# Drivetrain_control.net
KiCad netlist of a schematic drawn in EAGLE
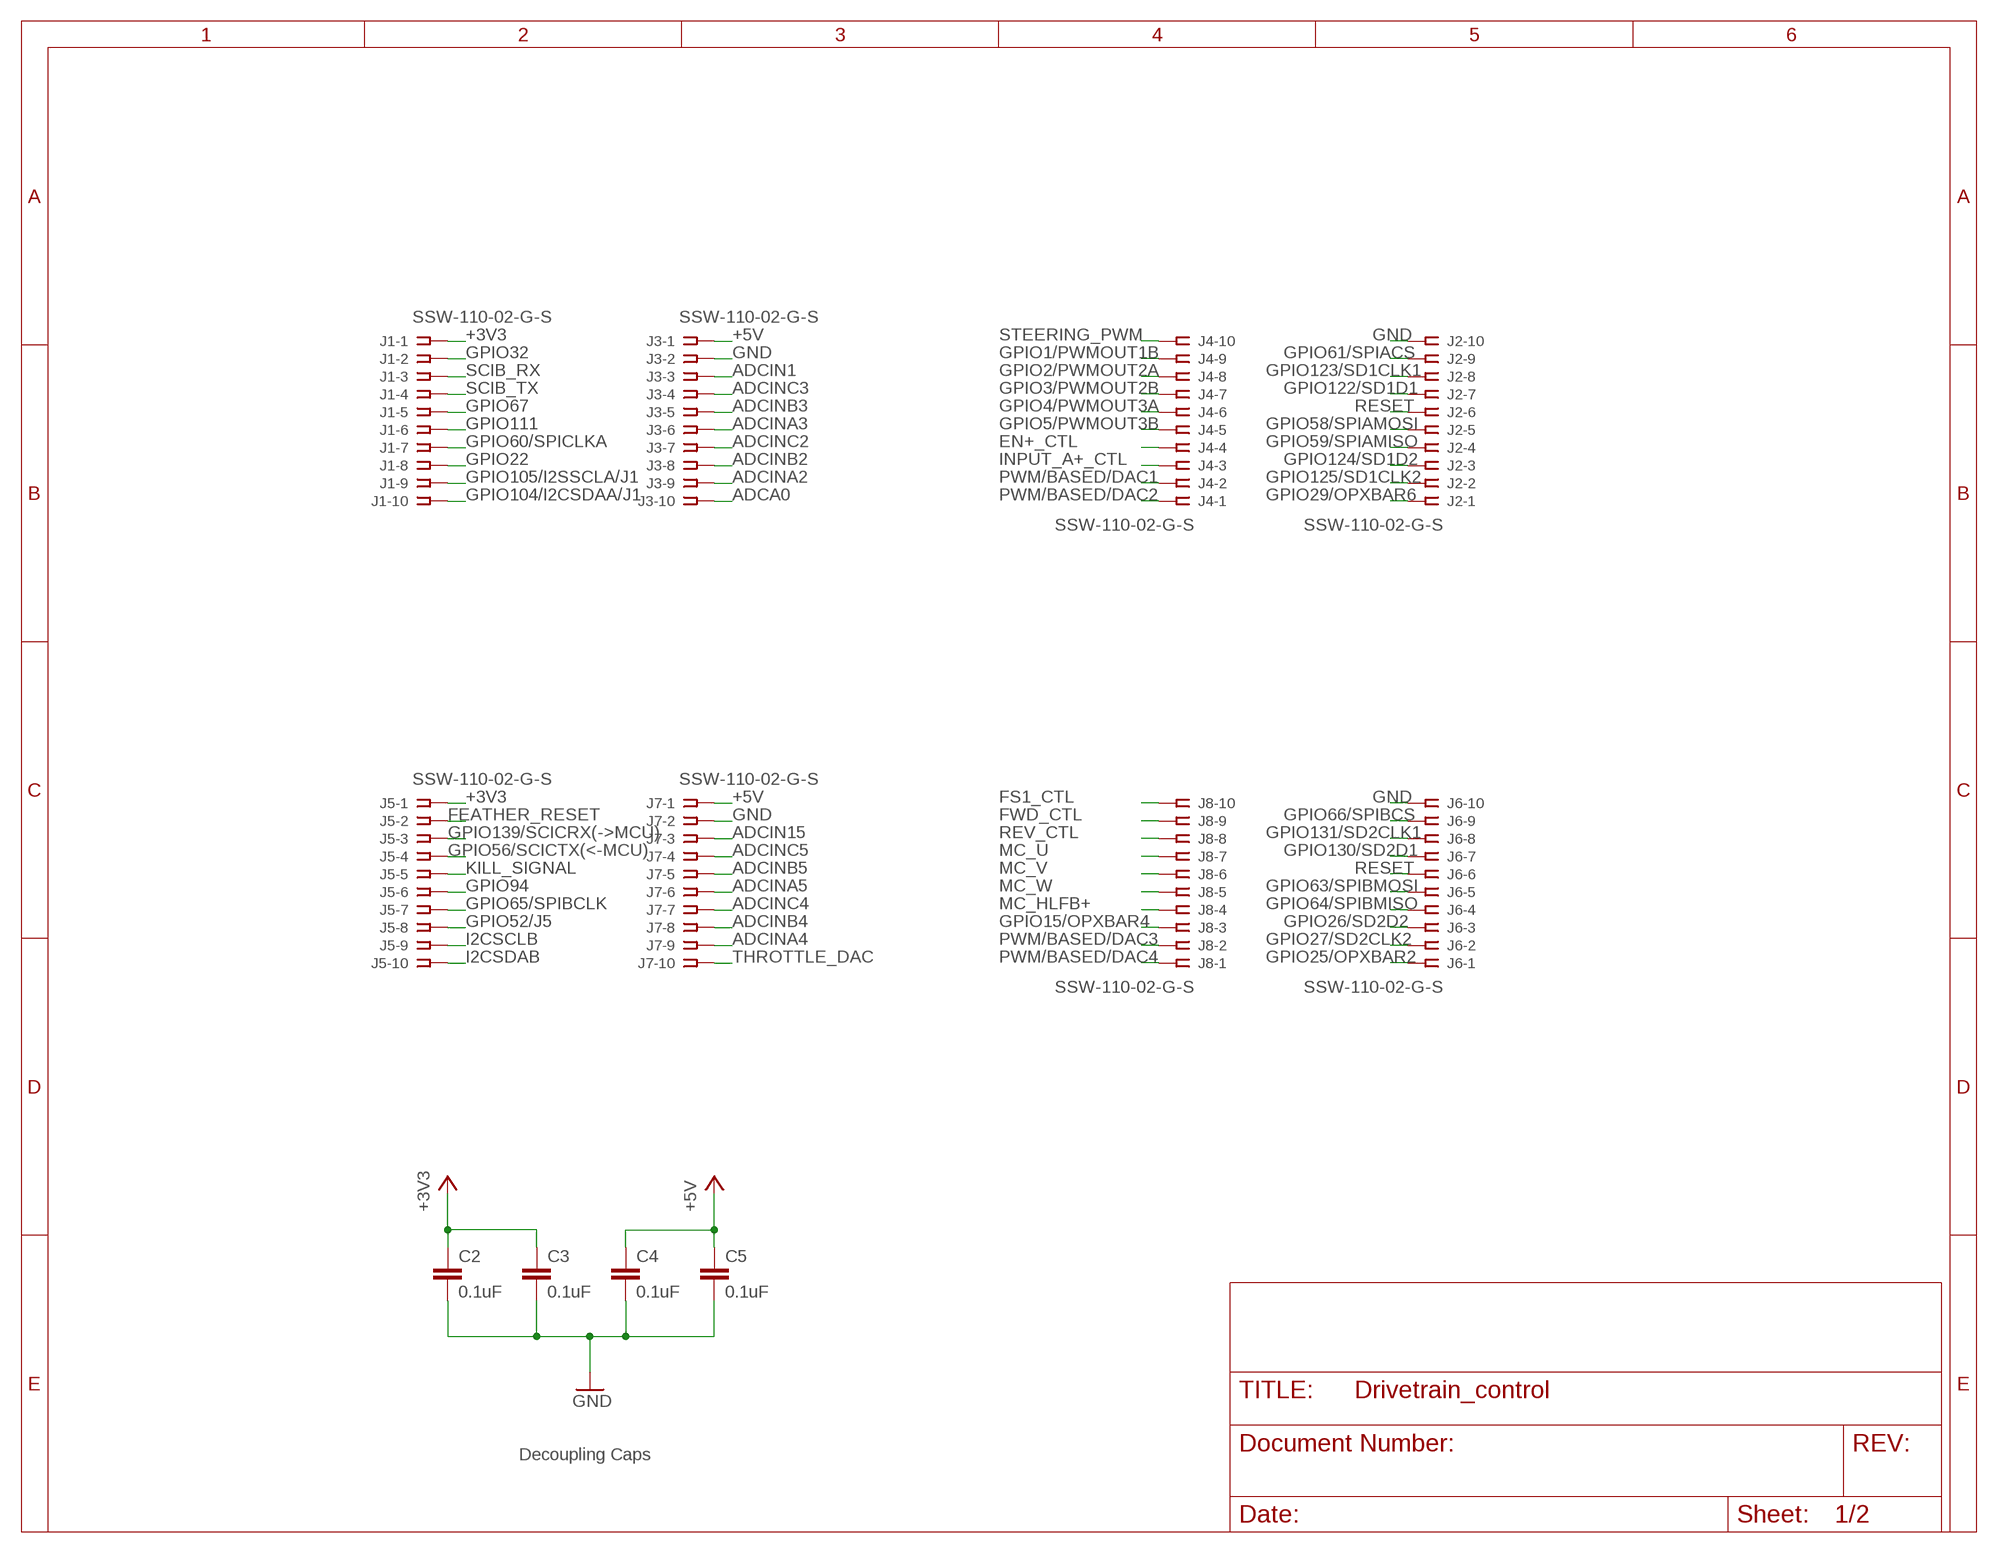
[diagram p0: schematic, sheet 1]
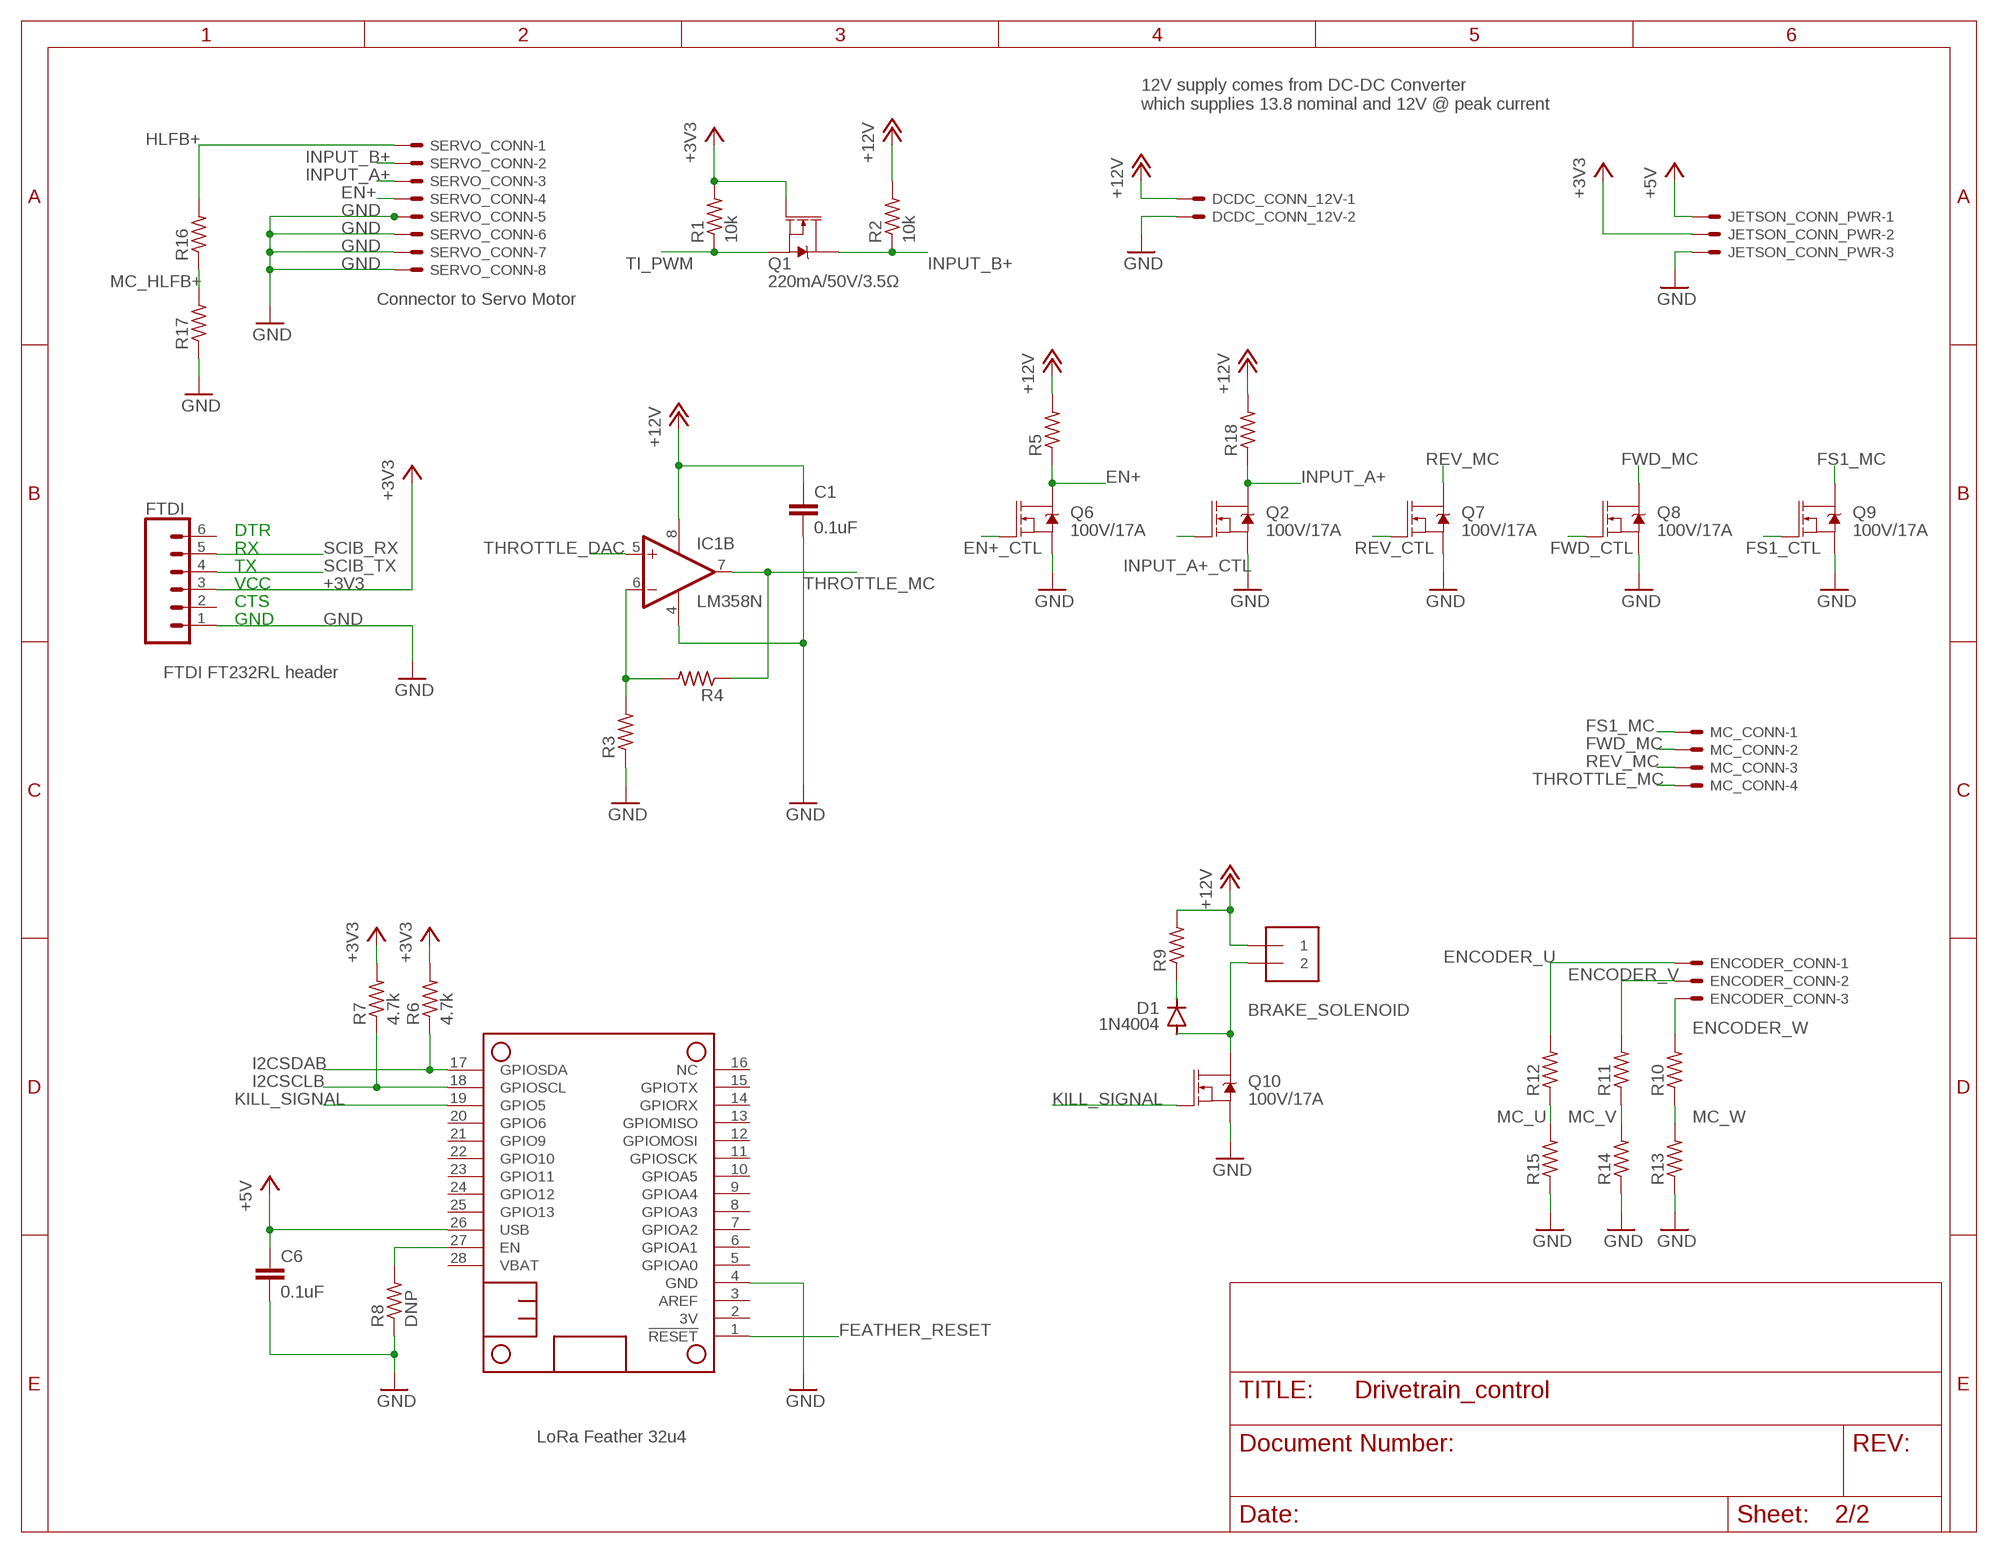
[diagram p1: schematic, sheet 2]

(export (version "E")
  (design (tool "Eeschema 10.0.6"))
  (components
    (comp (ref "BRAKE_CONN")
      (value "1X2-3.5MM")
      (footprint "eagle-import:1X2-3.5MM")
      (libsource (lib "eagle-import") (part "1X2-3.5MM"))
    )
    (comp (ref "C1")
      (value "0.1uF")
      (footprint "eagle-import:C0805")
      (libsource (lib "eagle-import") (part "C"))
    )
    (comp (ref "C6")
      (value "0.1uF")
      (footprint "eagle-import:C0805")
      (libsource (lib "eagle-import") (part "C"))
    )
    (comp (ref "D1")
      (value "1N4004")
      (footprint "eagle-import:DO41-10")
      (libsource (lib "eagle-import") (part "1N4004"))
    )
    (comp (ref "DCDC_CONN_12V")
      (value "22-23-2021")
      (footprint "eagle-import:22-23-2021")
      (fields (field (name "MF") "MOLEX"))
      (libsource (lib "eagle-import") (part "22-23-2021"))
    )
    (comp (ref "ENCODER_CONN")
      (value "22-23-2031")
      (footprint "eagle-import:22-23-2031")
      (fields (field (name "MF") "MOLEX"))
      (libsource (lib "eagle-import") (part "22-23-2031"))
    )
    (comp (ref "FTDI")
      (value "CONN_06LONGPADS")
      (footprint "eagle-import:1X06_LONGPADS")
      (libsource (lib "eagle-import") (part "CONN_06LONGPADS"))
    )
    (comp (ref "IC1")
      (value "LM358N")
      (footprint "eagle-import:DIL08")
      (libsource (lib "eagle-import") (part "LM358N"))
    )
    (comp (ref "JETSON_CONN_PWR")
      (value "22-23-2031")
      (footprint "eagle-import:22-23-2031")
      (fields (field (name "MF") "MOLEX"))
      (libsource (lib "eagle-import") (part "22-23-2031"))
    )
    (comp (ref "MC_CONN")
      (value "22-23-2041")
      (footprint "eagle-import:22-23-2041")
      (fields (field (name "MF") "MOLEX"))
      (libsource (lib "eagle-import") (part "22-23-2041"))
    )
    (comp (ref "MS1")
      (value "FEATHERWING_NODIM")
      (footprint "eagle-import:FEATHERWING_DIM")
      (libsource (lib "eagle-import") (part "FEATHERWING_NODIM"))
    )
    (comp (ref "Q1")
      (value "220mA/50V/3.5Ω")
      (footprint "eagle-import:SOT23-3")
      (libsource (lib "eagle-import") (part "MOSFET-NCH-BSS138"))
    )
    (comp (ref "Q2")
      (value "100V/17A")
      (footprint "eagle-import:TO220V")
      (libsource (lib "eagle-import") (part "MOSFET-NCH-FQP30N06L"))
    )
    (comp (ref "Q6")
      (value "100V/17A")
      (footprint "eagle-import:TO220V")
      (libsource (lib "eagle-import") (part "MOSFET-NCH-FQP30N06L"))
    )
    (comp (ref "Q7")
      (value "100V/17A")
      (footprint "eagle-import:TO220V")
      (libsource (lib "eagle-import") (part "MOSFET-NCH-FQP30N06L"))
    )
    (comp (ref "Q8")
      (value "100V/17A")
      (footprint "eagle-import:TO220V")
      (libsource (lib "eagle-import") (part "MOSFET-NCH-FQP30N06L"))
    )
    (comp (ref "Q9")
      (value "100V/17A")
      (footprint "eagle-import:TO220V")
      (libsource (lib "eagle-import") (part "MOSFET-NCH-FQP30N06L"))
    )
    (comp (ref "Q10")
      (value "100V/17A")
      (footprint "eagle-import:TO220V")
      (libsource (lib "eagle-import") (part "MOSFET-NCH-FQP30N06L"))
    )
    (comp (ref "R1")
      (value "10k")
      (footprint "eagle-import:R0805")
      (libsource (lib "eagle-import") (part "R-US_R0805"))
    )
    (comp (ref "R2")
      (value "10k")
      (footprint "eagle-import:R0805")
      (libsource (lib "eagle-import") (part "R-US_R0805"))
    )
    (comp (ref "R3")
      (value "R-US_R0805")
      (footprint "eagle-import:R0805")
      (libsource (lib "eagle-import") (part "R-US_R0805"))
    )
    (comp (ref "R4")
      (value "R-US_R0805")
      (footprint "eagle-import:R0805")
      (libsource (lib "eagle-import") (part "R-US_R0805"))
    )
    (comp (ref "R5")
      (value "R-US_R0805")
      (footprint "eagle-import:R0805")
      (libsource (lib "eagle-import") (part "R-US_R0805"))
    )
    (comp (ref "R6")
      (value "4.7k")
      (footprint "eagle-import:R0805")
      (libsource (lib "eagle-import") (part "R-US_R0805"))
    )
    (comp (ref "R7")
      (value "4.7k")
      (footprint "eagle-import:R0805")
      (libsource (lib "eagle-import") (part "R-US_R0805"))
    )
    (comp (ref "R8")
      (value "DNP")
      (footprint "eagle-import:R0805")
      (libsource (lib "eagle-import") (part "R-US_R0805"))
    )
    (comp (ref "R9")
      (value "R-US_R0805")
      (footprint "eagle-import:R0805")
      (libsource (lib "eagle-import") (part "R-US_R0805"))
    )
    (comp (ref "R10")
      (value "R-US_R0805")
      (footprint "eagle-import:R0805")
      (libsource (lib "eagle-import") (part "R-US_R0805"))
    )
    (comp (ref "R11")
      (value "R-US_R0805")
      (footprint "eagle-import:R0805")
      (libsource (lib "eagle-import") (part "R-US_R0805"))
    )
    (comp (ref "R12")
      (value "R-US_R0805")
      (footprint "eagle-import:R0805")
      (libsource (lib "eagle-import") (part "R-US_R0805"))
    )
    (comp (ref "R13")
      (value "R-US_R0805")
      (footprint "eagle-import:R0805")
      (libsource (lib "eagle-import") (part "R-US_R0805"))
    )
    (comp (ref "R14")
      (value "R-US_R0805")
      (footprint "eagle-import:R0805")
      (libsource (lib "eagle-import") (part "R-US_R0805"))
    )
    (comp (ref "R15")
      (value "R-US_R0805")
      (footprint "eagle-import:R0805")
      (libsource (lib "eagle-import") (part "R-US_R0805"))
    )
    (comp (ref "R16")
      (value "R-US_R0805")
      (footprint "eagle-import:R0805")
      (libsource (lib "eagle-import") (part "R-US_R0805"))
    )
    (comp (ref "R17")
      (value "R-US_R0805")
      (footprint "eagle-import:R0805")
      (libsource (lib "eagle-import") (part "R-US_R0805"))
    )
    (comp (ref "R18")
      (value "R-US_R0805")
      (footprint "eagle-import:R0805")
      (libsource (lib "eagle-import") (part "R-US_R0805"))
    )
    (comp (ref "SERVO_CONN")
      (value "5566-8")
      (footprint "eagle-import:5566-8")
      (fields (field (name "MF") "MOLEX"))
      (libsource (lib "eagle-import") (part "5566-8"))
    )
    (comp (ref "C2")
      (value "0.1uF")
      (footprint "eagle-import:C0805")
      (libsource (lib "eagle-import") (part "C"))
    )
    (comp (ref "C3")
      (value "0.1uF")
      (footprint "eagle-import:C0805")
      (libsource (lib "eagle-import") (part "C"))
    )
    (comp (ref "C4")
      (value "0.1uF")
      (footprint "eagle-import:C0805")
      (libsource (lib "eagle-import") (part "C"))
    )
    (comp (ref "C5")
      (value "0.1uF")
      (footprint "eagle-import:C0805")
      (libsource (lib "eagle-import") (part "C"))
    )
    (comp (ref "J1")
      (value "SSW-110-02-G-S")
      (footprint "eagle-import:SSW-110-02-G-S")
      (fields (field (name "MF") "Samtec Inc."))
      (libsource (lib "eagle-import") (part "SSW-110-02-G-S"))
    )
    (comp (ref "J2")
      (value "SSW-110-02-G-S")
      (footprint "eagle-import:SSW-110-02-G-S")
      (fields (field (name "MF") "Samtec Inc."))
      (libsource (lib "eagle-import") (part "SSW-110-02-G-S"))
    )
    (comp (ref "J3")
      (value "SSW-110-02-G-S")
      (footprint "eagle-import:SSW-110-02-G-S")
      (fields (field (name "MF") "Samtec Inc."))
      (libsource (lib "eagle-import") (part "SSW-110-02-G-S"))
    )
    (comp (ref "J4")
      (value "SSW-110-02-G-S")
      (footprint "eagle-import:SSW-110-02-G-S")
      (fields (field (name "MF") "Samtec Inc."))
      (libsource (lib "eagle-import") (part "SSW-110-02-G-S"))
    )
    (comp (ref "J5")
      (value "SSW-110-02-G-S")
      (footprint "eagle-import:SSW-110-02-G-S")
      (fields (field (name "MF") "Samtec Inc."))
      (libsource (lib "eagle-import") (part "SSW-110-02-G-S"))
    )
    (comp (ref "J6")
      (value "SSW-110-02-G-S")
      (footprint "eagle-import:SSW-110-02-G-S")
      (fields (field (name "MF") "Samtec Inc."))
      (libsource (lib "eagle-import") (part "SSW-110-02-G-S"))
    )
    (comp (ref "J7")
      (value "SSW-110-02-G-S")
      (footprint "eagle-import:SSW-110-02-G-S")
      (fields (field (name "MF") "Samtec Inc."))
      (libsource (lib "eagle-import") (part "SSW-110-02-G-S"))
    )
    (comp (ref "J8")
      (value "SSW-110-02-G-S")
      (footprint "eagle-import:SSW-110-02-G-S")
      (fields (field (name "MF") "Samtec Inc."))
      (libsource (lib "eagle-import") (part "SSW-110-02-G-S"))
    )
  )
  (nets
    (net (code "1") (name "+3V3") (class "Default")
      (node (ref "C2") (pin "1") (pinfunction "1_1") (pintype "passive"))
      (node (ref "C3") (pin "1") (pinfunction "1_1") (pintype "passive"))
      (node (ref "FTDI") (pin "3") (pinfunction "3_3") (pintype "passive"))
      (node (ref "J1") (pin "1") (pinfunction "1_1") (pintype "passive"))
      (node (ref "J5") (pin "1") (pinfunction "1_1") (pintype "passive"))
      (node (ref "JETSON_CONN_PWR") (pin "2") (pinfunction "S_2") (pintype "passive"))
      (node (ref "Q1") (pin "1") (pinfunction "G_1") (pintype "bidirectional"))
      (node (ref "R1") (pin "2") (pinfunction "2_2") (pintype "passive"))
      (node (ref "R6") (pin "2") (pinfunction "2_2") (pintype "passive"))
      (node (ref "R7") (pin "2") (pinfunction "2_2") (pintype "passive"))
    )
    (net (code "2") (name "+5V") (class "Default")
      (node (ref "C4") (pin "1") (pinfunction "1_1") (pintype "passive"))
      (node (ref "C5") (pin "1") (pinfunction "1_1") (pintype "passive"))
      (node (ref "C6") (pin "1") (pinfunction "1_1") (pintype "passive"))
      (node (ref "J3") (pin "1") (pinfunction "1_1") (pintype "passive"))
      (node (ref "J7") (pin "1") (pinfunction "1_1") (pintype "passive"))
      (node (ref "JETSON_CONN_PWR") (pin "1") (pinfunction "S_1") (pintype "passive"))
      (node (ref "MS1") (pin "26") (pinfunction "USB_26") (pintype "power_in"))
    )
    (net (code "3") (name "+12V") (class "Default")
      (node (ref "BRAKE_CONN") (pin "1") (pinfunction "1_1") (pintype "passive"))
      (node (ref "C1") (pin "1") (pinfunction "1_1") (pintype "passive"))
      (node (ref "DCDC_CONN_12V") (pin "1") (pinfunction "S_1") (pintype "passive"))
      (node (ref "IC1") (pin "8") (pinfunction "V+_8") (pintype "power_in"))
      (node (ref "R18") (pin "2") (pinfunction "2_2") (pintype "passive"))
      (node (ref "R2") (pin "2") (pinfunction "2_2") (pintype "passive"))
      (node (ref "R5") (pin "2") (pinfunction "2_2") (pintype "passive"))
      (node (ref "R9") (pin "2") (pinfunction "2_2") (pintype "passive"))
    )
    (net (code "4") (name "3V") (class "Default")
      (node (ref "MS1") (pin "2") (pinfunction "3V_2") (pintype "power_in"))
    )
    (net (code "5") (name "ADCA0") (class "Default")
      (node (ref "J3") (pin "10") (pinfunction "1_10") (pintype "passive"))
    )
    (net (code "6") (name "ADCIN1") (class "Default")
      (node (ref "J3") (pin "3") (pinfunction "1_3") (pintype "passive"))
    )
    (net (code "7") (name "ADCIN15") (class "Default")
      (node (ref "J7") (pin "3") (pinfunction "1_3") (pintype "passive"))
    )
    (net (code "8") (name "ADCINA2") (class "Default")
      (node (ref "J3") (pin "9") (pinfunction "1_9") (pintype "passive"))
    )
    (net (code "9") (name "ADCINA3") (class "Default")
      (node (ref "J3") (pin "6") (pinfunction "1_6") (pintype "passive"))
    )
    (net (code "10") (name "ADCINA4") (class "Default")
      (node (ref "J7") (pin "9") (pinfunction "1_9") (pintype "passive"))
    )
    (net (code "11") (name "ADCINA5") (class "Default")
      (node (ref "J7") (pin "6") (pinfunction "1_6") (pintype "passive"))
    )
    (net (code "12") (name "ADCINB2") (class "Default")
      (node (ref "J3") (pin "8") (pinfunction "1_8") (pintype "passive"))
    )
    (net (code "13") (name "ADCINB3") (class "Default")
      (node (ref "J3") (pin "5") (pinfunction "1_5") (pintype "passive"))
    )
    (net (code "14") (name "ADCINB4") (class "Default")
      (node (ref "J7") (pin "8") (pinfunction "1_8") (pintype "passive"))
    )
    (net (code "15") (name "ADCINB5") (class "Default")
      (node (ref "J7") (pin "5") (pinfunction "1_5") (pintype "passive"))
    )
    (net (code "16") (name "ADCINC2") (class "Default")
      (node (ref "J3") (pin "7") (pinfunction "1_7") (pintype "passive"))
    )
    (net (code "17") (name "ADCINC3") (class "Default")
      (node (ref "J3") (pin "4") (pinfunction "1_4") (pintype "passive"))
    )
    (net (code "18") (name "ADCINC4") (class "Default")
      (node (ref "J7") (pin "7") (pinfunction "1_7") (pintype "passive"))
    )
    (net (code "19") (name "ADCINC5") (class "Default")
      (node (ref "J7") (pin "4") (pinfunction "1_4") (pintype "passive"))
    )
    (net (code "20") (name "BRAKE_SOLENOID") (class "Default")
      (node (ref "BRAKE_CONN") (pin "2") (pinfunction "2_2") (pintype "passive"))
      (node (ref "D1") (pin "A") (pinfunction "A_A") (pintype "passive"))
      (node (ref "Q10") (pin "2") (pinfunction "D_2") (pintype "bidirectional"))
    )
    (net (code "21") (name "EN+") (class "Default")
      (node (ref "Q6") (pin "2") (pinfunction "D_2") (pintype "bidirectional"))
      (node (ref "R5") (pin "1") (pinfunction "1_1") (pintype "passive"))
      (node (ref "SERVO_CONN") (pin "4") (pinfunction "S_4") (pintype "passive"))
    )
    (net (code "22") (name "EN+_CTL") (class "Default")
      (node (ref "J4") (pin "4") (pinfunction "1_4") (pintype "passive"))
      (node (ref "Q6") (pin "1") (pinfunction "G_1") (pintype "bidirectional"))
    )
    (net (code "23") (name "ENCODER_U") (class "Default")
      (node (ref "ENCODER_CONN") (pin "1") (pinfunction "S_1") (pintype "passive"))
      (node (ref "R12") (pin "2") (pinfunction "2_2") (pintype "passive"))
    )
    (net (code "24") (name "ENCODER_V") (class "Default")
      (node (ref "ENCODER_CONN") (pin "2") (pinfunction "S_2") (pintype "passive"))
      (node (ref "R11") (pin "2") (pinfunction "2_2") (pintype "passive"))
    )
    (net (code "25") (name "ENCODER_W") (class "Default")
      (node (ref "ENCODER_CONN") (pin "3") (pinfunction "S_3") (pintype "passive"))
      (node (ref "R10") (pin "2") (pinfunction "2_2") (pintype "passive"))
    )
    (net (code "26") (name "FEATHER_RESET") (class "Default")
      (node (ref "J5") (pin "2") (pinfunction "1_2") (pintype "passive"))
      (node (ref "MS1") (pin "1") (pinfunction "~{RESET}_1") (pintype "input"))
    )
    (net (code "27") (name "FS1_CTL") (class "Default")
      (node (ref "J8") (pin "10") (pinfunction "1_10") (pintype "passive"))
      (node (ref "Q9") (pin "1") (pinfunction "G_1") (pintype "bidirectional"))
    )
    (net (code "28") (name "FS1_MC") (class "Default")
      (node (ref "MC_CONN") (pin "1") (pinfunction "S_1") (pintype "passive"))
      (node (ref "Q9") (pin "2") (pinfunction "D_2") (pintype "bidirectional"))
    )
    (net (code "29") (name "FWD_CTL") (class "Default")
      (node (ref "J8") (pin "9") (pinfunction "1_9") (pintype "passive"))
      (node (ref "Q8") (pin "1") (pinfunction "G_1") (pintype "bidirectional"))
    )
    (net (code "30") (name "FWD_MC") (class "Default")
      (node (ref "MC_CONN") (pin "2") (pinfunction "S_2") (pintype "passive"))
      (node (ref "Q8") (pin "2") (pinfunction "D_2") (pintype "bidirectional"))
    )
    (net (code "31") (name "GND") (class "Default")
      (node (ref "C1") (pin "2") (pinfunction "2_2") (pintype "passive"))
      (node (ref "C2") (pin "2") (pinfunction "2_2") (pintype "passive"))
      (node (ref "C3") (pin "2") (pinfunction "2_2") (pintype "passive"))
      (node (ref "C4") (pin "2") (pinfunction "2_2") (pintype "passive"))
      (node (ref "C5") (pin "2") (pinfunction "2_2") (pintype "passive"))
      (node (ref "C6") (pin "2") (pinfunction "2_2") (pintype "passive"))
      (node (ref "DCDC_CONN_12V") (pin "2") (pinfunction "S_2") (pintype "passive"))
      (node (ref "FTDI") (pin "1") (pinfunction "1_1") (pintype "passive"))
      (node (ref "IC1") (pin "4") (pinfunction "V-_4") (pintype "power_in"))
      (node (ref "J2") (pin "10") (pinfunction "1_10") (pintype "passive"))
      (node (ref "J3") (pin "2") (pinfunction "1_2") (pintype "passive"))
      (node (ref "J6") (pin "10") (pinfunction "1_10") (pintype "passive"))
      (node (ref "J7") (pin "2") (pinfunction "1_2") (pintype "passive"))
      (node (ref "JETSON_CONN_PWR") (pin "3") (pinfunction "S_3") (pintype "passive"))
      (node (ref "MS1") (pin "4") (pinfunction "GND_4") (pintype "power_in"))
      (node (ref "Q10") (pin "3") (pinfunction "S_3") (pintype "bidirectional"))
      (node (ref "Q2") (pin "3") (pinfunction "S_3") (pintype "bidirectional"))
      (node (ref "Q6") (pin "3") (pinfunction "S_3") (pintype "bidirectional"))
      (node (ref "Q7") (pin "3") (pinfunction "S_3") (pintype "bidirectional"))
      (node (ref "Q8") (pin "3") (pinfunction "S_3") (pintype "bidirectional"))
      (node (ref "Q9") (pin "3") (pinfunction "S_3") (pintype "bidirectional"))
      (node (ref "R13") (pin "1") (pinfunction "1_1") (pintype "passive"))
      (node (ref "R14") (pin "1") (pinfunction "1_1") (pintype "passive"))
      (node (ref "R15") (pin "1") (pinfunction "1_1") (pintype "passive"))
      (node (ref "R17") (pin "1") (pinfunction "1_1") (pintype "passive"))
      (node (ref "R3") (pin "1") (pinfunction "1_1") (pintype "passive"))
      (node (ref "R8") (pin "1") (pinfunction "1_1") (pintype "passive"))
      (node (ref "SERVO_CONN") (pin "5") (pinfunction "S_5") (pintype "passive"))
      (node (ref "SERVO_CONN") (pin "6") (pinfunction "S_6") (pintype "passive"))
      (node (ref "SERVO_CONN") (pin "7") (pinfunction "S_7") (pintype "passive"))
      (node (ref "SERVO_CONN") (pin "8") (pinfunction "S_8") (pintype "passive"))
    )
    (net (code "32") (name "GPIO1{slash}PWMOUT1B") (class "Default")
      (node (ref "J4") (pin "9") (pinfunction "1_9") (pintype "passive"))
    )
    (net (code "33") (name "GPIO2{slash}PWMOUT2A") (class "Default")
      (node (ref "J4") (pin "8") (pinfunction "1_8") (pintype "passive"))
    )
    (net (code "34") (name "GPIO3{slash}PWMOUT2B") (class "Default")
      (node (ref "J4") (pin "7") (pinfunction "1_7") (pintype "passive"))
    )
    (net (code "35") (name "GPIO4{slash}PWMOUT3A") (class "Default")
      (node (ref "J4") (pin "6") (pinfunction "1_6") (pintype "passive"))
    )
    (net (code "36") (name "GPIO5{slash}PWMOUT3B") (class "Default")
      (node (ref "J4") (pin "5") (pinfunction "1_5") (pintype "passive"))
    )
    (net (code "37") (name "GPIO15{slash}OPXBAR4") (class "Default")
      (node (ref "J8") (pin "3") (pinfunction "1_3") (pintype "passive"))
    )
    (net (code "38") (name "GPIO22") (class "Default")
      (node (ref "J1") (pin "8") (pinfunction "1_8") (pintype "passive"))
    )
    (net (code "39") (name "GPIO25{slash}OPXBAR2") (class "Default")
      (node (ref "J6") (pin "1") (pinfunction "1_1") (pintype "passive"))
    )
    (net (code "40") (name "GPIO26{slash}SD2D2") (class "Default")
      (node (ref "J6") (pin "3") (pinfunction "1_3") (pintype "passive"))
    )
    (net (code "41") (name "GPIO27{slash}SD2CLK2") (class "Default")
      (node (ref "J6") (pin "2") (pinfunction "1_2") (pintype "passive"))
    )
    (net (code "42") (name "GPIO29{slash}OPXBAR6") (class "Default")
      (node (ref "J2") (pin "1") (pinfunction "1_1") (pintype "passive"))
    )
    (net (code "43") (name "GPIO32") (class "Default")
      (node (ref "J1") (pin "2") (pinfunction "1_2") (pintype "passive"))
    )
    (net (code "44") (name "GPIO52{slash}J5") (class "Default")
      (node (ref "J5") (pin "8") (pinfunction "1_8") (pintype "passive"))
    )
    (net (code "45") (name "GPIO56{slash}SCICTX(<-MCU)") (class "Default")
      (node (ref "J5") (pin "4") (pinfunction "1_4") (pintype "passive"))
    )
    (net (code "46") (name "GPIO58{slash}SPIAMOSI") (class "Default")
      (node (ref "J2") (pin "5") (pinfunction "1_5") (pintype "passive"))
    )
    (net (code "47") (name "GPIO59{slash}SPIAMISO") (class "Default")
      (node (ref "J2") (pin "4") (pinfunction "1_4") (pintype "passive"))
    )
    (net (code "48") (name "GPIO60{slash}SPICLKA") (class "Default")
      (node (ref "J1") (pin "7") (pinfunction "1_7") (pintype "passive"))
    )
    (net (code "49") (name "GPIO61{slash}SPIACS") (class "Default")
      (node (ref "J2") (pin "9") (pinfunction "1_9") (pintype "passive"))
    )
    (net (code "50") (name "GPIO63{slash}SPIBMOSI") (class "Default")
      (node (ref "J6") (pin "5") (pinfunction "1_5") (pintype "passive"))
    )
    (net (code "51") (name "GPIO64{slash}SPIBMISO") (class "Default")
      (node (ref "J6") (pin "4") (pinfunction "1_4") (pintype "passive"))
    )
    (net (code "52") (name "GPIO65{slash}SPIBCLK") (class "Default")
      (node (ref "J5") (pin "7") (pinfunction "1_7") (pintype "passive"))
    )
    (net (code "53") (name "GPIO66{slash}SPIBCS") (class "Default")
      (node (ref "J6") (pin "9") (pinfunction "1_9") (pintype "passive"))
    )
    (net (code "54") (name "GPIO67") (class "Default")
      (node (ref "J1") (pin "5") (pinfunction "1_5") (pintype "passive"))
    )
    (net (code "55") (name "GPIO94") (class "Default")
      (node (ref "J5") (pin "6") (pinfunction "1_6") (pintype "passive"))
    )
    (net (code "56") (name "GPIO104{slash}I2CSDAA{slash}J1") (class "Default")
      (node (ref "J1") (pin "10") (pinfunction "1_10") (pintype "passive"))
    )
    (net (code "57") (name "GPIO105{slash}I2SSCLA{slash}J1") (class "Default")
      (node (ref "J1") (pin "9") (pinfunction "1_9") (pintype "passive"))
    )
    (net (code "58") (name "GPIO111") (class "Default")
      (node (ref "J1") (pin "6") (pinfunction "1_6") (pintype "passive"))
    )
    (net (code "59") (name "GPIO122{slash}SD1D1") (class "Default")
      (node (ref "J2") (pin "7") (pinfunction "1_7") (pintype "passive"))
    )
    (net (code "60") (name "GPIO123{slash}SD1CLK1") (class "Default")
      (node (ref "J2") (pin "8") (pinfunction "1_8") (pintype "passive"))
    )
    (net (code "61") (name "GPIO124{slash}SD1D2") (class "Default")
      (node (ref "J2") (pin "3") (pinfunction "1_3") (pintype "passive"))
    )
    (net (code "62") (name "GPIO125{slash}SD1CLK2") (class "Default")
      (node (ref "J2") (pin "2") (pinfunction "1_2") (pintype "passive"))
    )
    (net (code "63") (name "GPIO130{slash}SD2D1") (class "Default")
      (node (ref "J6") (pin "7") (pinfunction "1_7") (pintype "passive"))
    )
    (net (code "64") (name "GPIO131{slash}SD2CLK1") (class "Default")
      (node (ref "J6") (pin "8") (pinfunction "1_8") (pintype "passive"))
    )
    (net (code "65") (name "GPIO139{slash}SCICRX(->MCU)") (class "Default")
      (node (ref "J5") (pin "3") (pinfunction "1_3") (pintype "passive"))
    )
    (net (code "66") (name "HLFB+") (class "Default")
      (node (ref "R16") (pin "2") (pinfunction "2_2") (pintype "passive"))
      (node (ref "SERVO_CONN") (pin "1") (pinfunction "S_1") (pintype "passive"))
    )
    (net (code "67") (name "I2CSCLB") (class "Default")
      (node (ref "J5") (pin "9") (pinfunction "1_9") (pintype "passive"))
      (node (ref "MS1") (pin "18") (pinfunction "GPIOSCL_18") (pintype "bidirectional"))
      (node (ref "R7") (pin "1") (pinfunction "1_1") (pintype "passive"))
    )
    (net (code "68") (name "I2CSDAB") (class "Default")
      (node (ref "J5") (pin "10") (pinfunction "1_10") (pintype "passive"))
      (node (ref "MS1") (pin "17") (pinfunction "GPIOSDA_17") (pintype "bidirectional"))
      (node (ref "R6") (pin "1") (pinfunction "1_1") (pintype "passive"))
    )
    (net (code "69") (name "INPUT_A+") (class "Default")
      (node (ref "Q2") (pin "2") (pinfunction "D_2") (pintype "bidirectional"))
      (node (ref "R18") (pin "1") (pinfunction "1_1") (pintype "passive"))
      (node (ref "SERVO_CONN") (pin "3") (pinfunction "S_3") (pintype "passive"))
    )
    (net (code "70") (name "INPUT_A+_CTL") (class "Default")
      (node (ref "J4") (pin "3") (pinfunction "1_3") (pintype "passive"))
      (node (ref "Q2") (pin "1") (pinfunction "G_1") (pintype "bidirectional"))
    )
    (net (code "71") (name "INPUT_B+") (class "Default")
      (node (ref "Q1") (pin "3") (pinfunction "D_3") (pintype "bidirectional"))
      (node (ref "R2") (pin "1") (pinfunction "1_1") (pintype "passive"))
      (node (ref "SERVO_CONN") (pin "2") (pinfunction "S_2") (pintype "passive"))
    )
    (net (code "72") (name "KILL_SIGNAL") (class "Default")
      (node (ref "J5") (pin "5") (pinfunction "1_5") (pintype "passive"))
      (node (ref "MS1") (pin "19") (pinfunction "GPIO5_19") (pintype "bidirectional"))
      (node (ref "Q10") (pin "1") (pinfunction "G_1") (pintype "bidirectional"))
    )
    (net (code "73") (name "MC_HLFB+") (class "Default")
      (node (ref "J8") (pin "4") (pinfunction "1_4") (pintype "passive"))
      (node (ref "R16") (pin "1") (pinfunction "1_1") (pintype "passive"))
      (node (ref "R17") (pin "2") (pinfunction "2_2") (pintype "passive"))
    )
    (net (code "74") (name "MC_U") (class "Default")
      (node (ref "J8") (pin "7") (pinfunction "1_7") (pintype "passive"))
      (node (ref "R12") (pin "1") (pinfunction "1_1") (pintype "passive"))
      (node (ref "R15") (pin "2") (pinfunction "2_2") (pintype "passive"))
    )
    (net (code "75") (name "MC_V") (class "Default")
      (node (ref "J8") (pin "6") (pinfunction "1_6") (pintype "passive"))
      (node (ref "R11") (pin "1") (pinfunction "1_1") (pintype "passive"))
      (node (ref "R14") (pin "2") (pinfunction "2_2") (pintype "passive"))
    )
    (net (code "76") (name "MC_W") (class "Default")
      (node (ref "J8") (pin "5") (pinfunction "1_5") (pintype "passive"))
      (node (ref "R10") (pin "1") (pinfunction "1_1") (pintype "passive"))
      (node (ref "R13") (pin "2") (pinfunction "2_2") (pintype "passive"))
    )
    (net (code "77") (name "Net-(D1-PadC)") (class "Default")
      (node (ref "D1") (pin "C") (pinfunction "C_C") (pintype "passive"))
      (node (ref "R9") (pin "1") (pinfunction "1_1") (pintype "passive"))
    )
    (net (code "78") (name "Net-(IC1B--IN)") (class "Default")
      (node (ref "IC1") (pin "6") (pinfunction "-IN_6") (pintype "input"))
      (node (ref "R3") (pin "2") (pinfunction "2_2") (pintype "passive"))
      (node (ref "R4") (pin "2") (pinfunction "2_2") (pintype "passive"))
    )
    (net (code "79") (name "Net-(MS1-EN)") (class "Default")
      (node (ref "MS1") (pin "27") (pinfunction "EN_27") (pintype "passive"))
      (node (ref "R8") (pin "2") (pinfunction "2_2") (pintype "passive"))
    )
    (net (code "80") (name "PWM{slash}BASED{slash}DAC1") (class "Default")
      (node (ref "J4") (pin "2") (pinfunction "1_2") (pintype "passive"))
    )
    (net (code "81") (name "PWM{slash}BASED{slash}DAC2") (class "Default")
      (node (ref "J4") (pin "1") (pinfunction "1_1") (pintype "passive"))
    )
    (net (code "82") (name "PWM{slash}BASED{slash}DAC3") (class "Default")
      (node (ref "J8") (pin "2") (pinfunction "1_2") (pintype "passive"))
    )
    (net (code "83") (name "PWM{slash}BASED{slash}DAC4") (class "Default")
      (node (ref "J8") (pin "1") (pinfunction "1_1") (pintype "passive"))
    )
    (net (code "84") (name "RESET") (class "Default")
      (node (ref "J2") (pin "6") (pinfunction "1_6") (pintype "passive"))
      (node (ref "J6") (pin "6") (pinfunction "1_6") (pintype "passive"))
    )
    (net (code "85") (name "REV_CTL") (class "Default")
      (node (ref "J8") (pin "8") (pinfunction "1_8") (pintype "passive"))
      (node (ref "Q7") (pin "1") (pinfunction "G_1") (pintype "bidirectional"))
    )
    (net (code "86") (name "REV_MC") (class "Default")
      (node (ref "MC_CONN") (pin "3") (pinfunction "S_3") (pintype "passive"))
      (node (ref "Q7") (pin "2") (pinfunction "D_2") (pintype "bidirectional"))
    )
    (net (code "87") (name "SCIB_RX") (class "Default")
      (node (ref "FTDI") (pin "5") (pinfunction "5_5") (pintype "passive"))
      (node (ref "J1") (pin "3") (pinfunction "1_3") (pintype "passive"))
    )
    (net (code "88") (name "SCIB_TX") (class "Default")
      (node (ref "FTDI") (pin "4") (pinfunction "4_4") (pintype "passive"))
      (node (ref "J1") (pin "4") (pinfunction "1_4") (pintype "passive"))
    )
    (net (code "89") (name "STEERING_PWM") (class "Default")
      (node (ref "J4") (pin "10") (pinfunction "1_10") (pintype "passive"))
    )
    (net (code "90") (name "THROTTLE_DAC") (class "Default")
      (node (ref "IC1") (pin "5") (pinfunction "+IN_5") (pintype "input"))
      (node (ref "J7") (pin "10") (pinfunction "1_10") (pintype "passive"))
    )
    (net (code "91") (name "THROTTLE_MC") (class "Default")
      (node (ref "IC1") (pin "7") (pinfunction "OUT_7") (pintype "output"))
      (node (ref "MC_CONN") (pin "4") (pinfunction "S_4") (pintype "passive"))
      (node (ref "R4") (pin "1") (pinfunction "1_1") (pintype "passive"))
    )
    (net (code "92") (name "TI_PWM") (class "Default")
      (node (ref "Q1") (pin "2") (pinfunction "S_2") (pintype "bidirectional"))
      (node (ref "R1") (pin "1") (pinfunction "1_1") (pintype "passive"))
    )
    (net (code "93") (name "VBAT") (class "Default")
      (node (ref "MS1") (pin "28") (pinfunction "VBAT_28") (pintype "power_in"))
    )
    (net (code "94") (name "unconnected-(FTDI-Pad2)") (class "Default")
      (node (ref "FTDI") (pin "2") (pinfunction "2_2") (pintype "passive"))
    )
    (net (code "95") (name "unconnected-(FTDI-Pad6)") (class "Default")
      (node (ref "FTDI") (pin "6") (pinfunction "6_6") (pintype "passive"))
    )
    (net (code "96") (name "unconnected-(MS1-AREF-Pad3)") (class "Default")
      (node (ref "MS1") (pin "3") (pinfunction "AREF_3") (pintype "passive"))
    )
    (net (code "97") (name "unconnected-(MS1-GPIO6-Pad20)") (class "Default")
      (node (ref "MS1") (pin "20") (pinfunction "GPIO6_20") (pintype "bidirectional"))
    )
    (net (code "98") (name "unconnected-(MS1-GPIO9-Pad21)") (class "Default")
      (node (ref "MS1") (pin "21") (pinfunction "GPIO9_21") (pintype "bidirectional"))
    )
    (net (code "99") (name "unconnected-(MS1-GPIO10-Pad22)") (class "Default")
      (node (ref "MS1") (pin "22") (pinfunction "GPIO10_22") (pintype "bidirectional"))
    )
    (net (code "100") (name "unconnected-(MS1-GPIO11-Pad23)") (class "Default")
      (node (ref "MS1") (pin "23") (pinfunction "GPIO11_23") (pintype "bidirectional"))
    )
    (net (code "101") (name "unconnected-(MS1-GPIO12-Pad24)") (class "Default")
      (node (ref "MS1") (pin "24") (pinfunction "GPIO12_24") (pintype "bidirectional"))
    )
    (net (code "102") (name "unconnected-(MS1-GPIO13-Pad25)") (class "Default")
      (node (ref "MS1") (pin "25") (pinfunction "GPIO13_25") (pintype "bidirectional"))
    )
    (net (code "103") (name "unconnected-(MS1-GPIOA0-Pad5)") (class "Default")
      (node (ref "MS1") (pin "5") (pinfunction "GPIOA0_5") (pintype "bidirectional"))
    )
    (net (code "104") (name "unconnected-(MS1-GPIOA1-Pad6)") (class "Default")
      (node (ref "MS1") (pin "6") (pinfunction "GPIOA1_6") (pintype "bidirectional"))
    )
    (net (code "105") (name "unconnected-(MS1-GPIOA2-Pad7)") (class "Default")
      (node (ref "MS1") (pin "7") (pinfunction "GPIOA2_7") (pintype "bidirectional"))
    )
    (net (code "106") (name "unconnected-(MS1-GPIOA3-Pad8)") (class "Default")
      (node (ref "MS1") (pin "8") (pinfunction "GPIOA3_8") (pintype "bidirectional"))
    )
    (net (code "107") (name "unconnected-(MS1-GPIOA4-Pad9)") (class "Default")
      (node (ref "MS1") (pin "9") (pinfunction "GPIOA4_9") (pintype "bidirectional"))
    )
    (net (code "108") (name "unconnected-(MS1-GPIOA5-Pad10)") (class "Default")
      (node (ref "MS1") (pin "10") (pinfunction "GPIOA5_10") (pintype "bidirectional"))
    )
    (net (code "109") (name "unconnected-(MS1-GPIOMISO-Pad13)") (class "Default")
      (node (ref "MS1") (pin "13") (pinfunction "GPIOMISO_13") (pintype "bidirectional"))
    )
    (net (code "110") (name "unconnected-(MS1-GPIOMOSI-Pad12)") (class "Default")
      (node (ref "MS1") (pin "12") (pinfunction "GPIOMOSI_12") (pintype "bidirectional"))
    )
    (net (code "111") (name "unconnected-(MS1-GPIORX-Pad14)") (class "Default")
      (node (ref "MS1") (pin "14") (pinfunction "GPIORX_14") (pintype "bidirectional"))
    )
    (net (code "112") (name "unconnected-(MS1-GPIOSCK-Pad11)") (class "Default")
      (node (ref "MS1") (pin "11") (pinfunction "GPIOSCK_11") (pintype "bidirectional"))
    )
    (net (code "113") (name "unconnected-(MS1-GPIOTX-Pad15)") (class "Default")
      (node (ref "MS1") (pin "15") (pinfunction "GPIOTX_15") (pintype "bidirectional"))
    )
    (net (code "114") (name "unconnected-(MS1-NC-Pad16)") (class "Default")
      (node (ref "MS1") (pin "16") (pinfunction "NC_16") (pintype "passive"))
    )
  )
)
